# Motor-X.net
KiCad netlist of a schematic drawn in Altium Designer
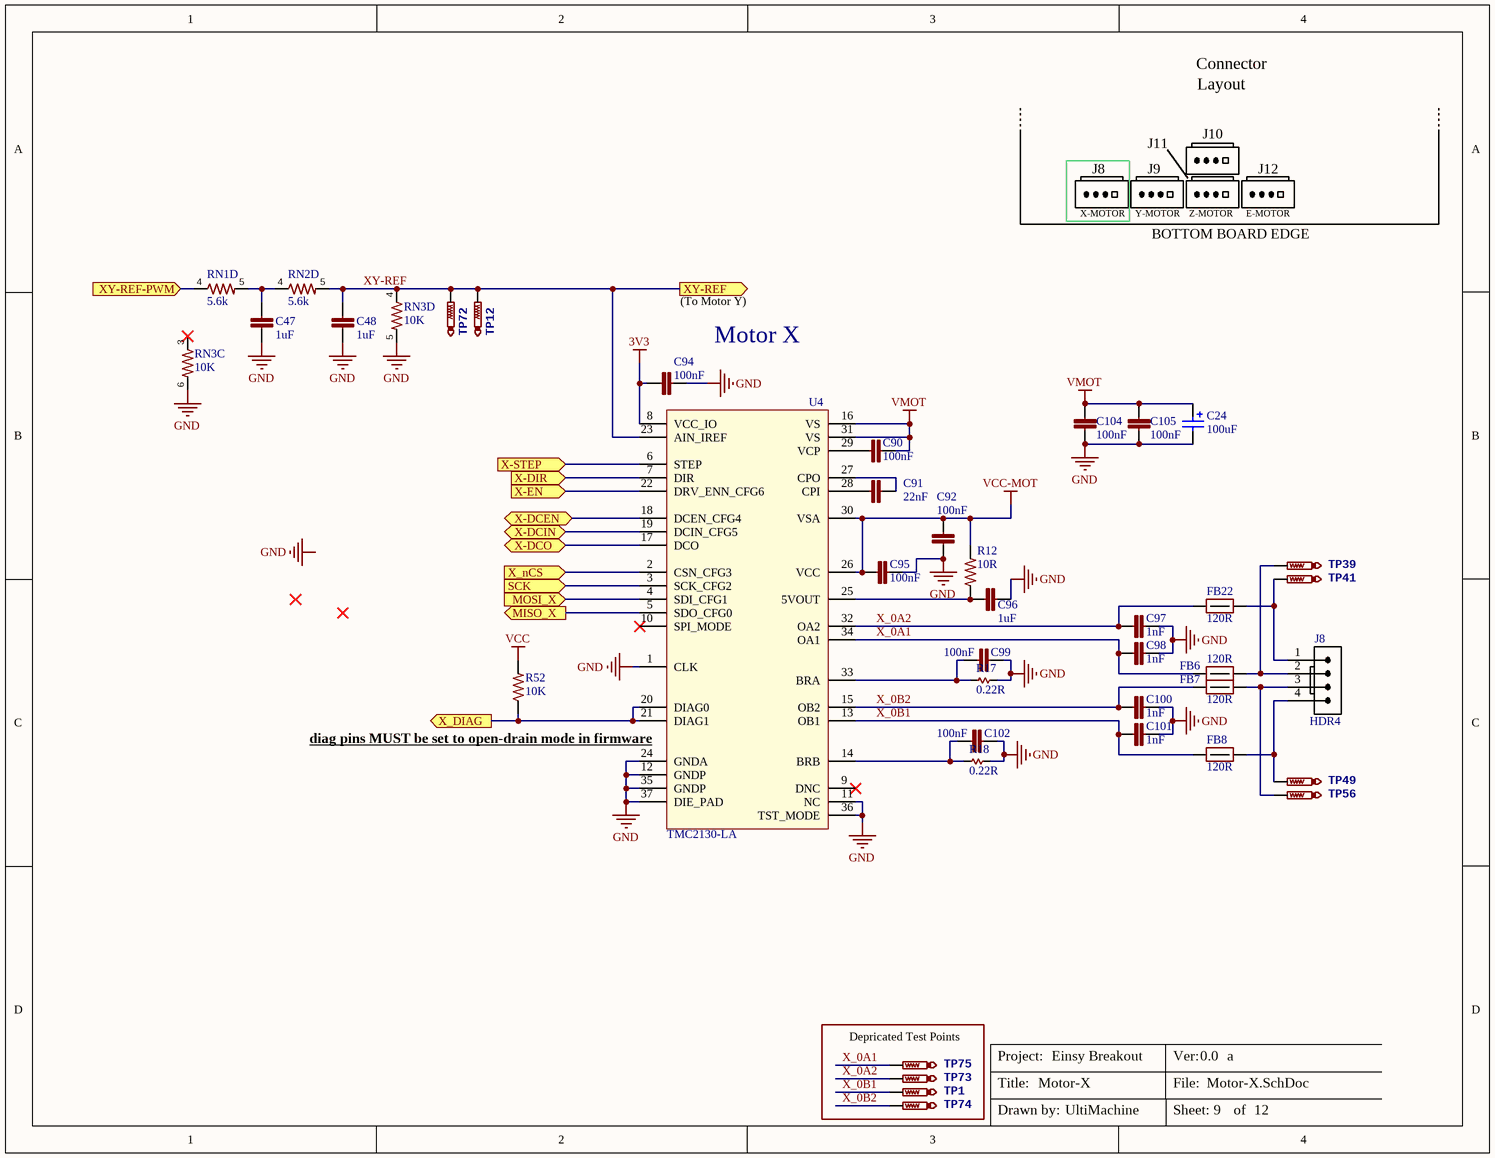
[diagram p0: Motor-X.SchDoc]

(export (version "E")
  (design (tool "Eeschema 10.0.6"))
  (components
    (comp (ref "C24")
      (value "100uF")
      (footprint "CAP-ELEC-063063077")
      (description "CAP ALUM 100UF 35V 20% SMD")
      (fields (field (name "MANUFACTURER") "Nichicon") (field (name "TOLERANCE") "+/- 20%"))
      (libsource (lib "3Delight") (part "UWT1V101MCL1GS"))
    )
    (comp (ref "C47")
      (value "1uF")
      (footprint "C0402")
      (description "CAP CER 0402 1uF 6.3V 10% X5R")
      (fields (field (name "MANUFACTURER") "Murata") (field (name "TOLERANCE") "+/- 10%"))
      (libsource (lib "3Delight") (part "GRM155R60J105KE19D"))
    )
    (comp (ref "C48")
      (value "1uF")
      (footprint "C0402")
      (description "CAP CER 0402 1uF 6.3V 10% X5R")
      (fields (field (name "MANUFACTURER") "Murata") (field (name "TOLERANCE") "+/- 10%"))
      (libsource (lib "3Delight") (part "GRM155R60J105KE19D"))
    )
    (comp (ref "C90")
      (value "100nF")
      (footprint "C0603")
      (description "CAP CER 0603 100nF 50V 10% X7R")
      (fields (field (name "MANUFACTURER") "Kemet") (field (name "TOLERANCE") "+/- 10%"))
      (libsource (lib "") (part "C0603C104K5RACTU_1"))
    )
    (comp (ref "C91")
      (value "22nF")
      (footprint "C0402")
      (description "CAP CER 0402 22nF ±10% 50V X7R")
      (fields (field (name "MANUFACTURER") "YAGEO") (field (name "TOLERANCE") "+/- 10%"))
      (libsource (lib "3Delight") (part "GCM155R71H223KA55D"))
    )
    (comp (ref "C92")
      (value "100nF")
      (footprint "C0402")
      (description "CAP CER 0402 100nF 16V 10% X7R")
      (fields (field (name "MANUFACTURER") "Murata") (field (name "TOLERANCE") "+/- 10%"))
      (libsource (lib "3Delight") (part "GRM155R71C104KA88D"))
    )
    (comp (ref "C94")
      (value "100nF")
      (footprint "C0402")
      (description "CAP CER 0402 100nF 16V 10% X7R")
      (fields (field (name "MANUFACTURER") "Murata") (field (name "TOLERANCE") "+/- 10%"))
      (libsource (lib "") (part "GRM155R71C104KA88D_1"))
    )
    (comp (ref "C95")
      (value "100nF")
      (footprint "C0402")
      (description "CAP CER 0402 100nF 16V 10% X7R")
      (fields (field (name "MANUFACTURER") "Murata") (field (name "TOLERANCE") "+/- 10%"))
      (libsource (lib "") (part "GRM155R71C104KA88D_1"))
    )
    (comp (ref "C96")
      (value "1uF")
      (footprint "C0402")
      (description "CAP CER 0402 1uF 6.3V 10% X5R")
      (fields (field (name "MANUFACTURER") "Murata") (field (name "TOLERANCE") "+/- 10%"))
      (libsource (lib "") (part "GRM155R60J105KE19D_1"))
    )
    (comp (ref "C97")
      (value "1nF")
      (footprint "C0603")
      (description "CAP CER 0603  1nF 50v 10% X7R")
      (fields (field (name "MANUFACTURER") "Kemet") (field (name "TOLERANCE") "+/- 10%"))
      (libsource (lib "3Delight") (part "C0603C102K5RACTU"))
    )
    (comp (ref "C98")
      (value "1nF")
      (footprint "C0603")
      (description "CAP CER 0603  1nF 50v 10% X7R")
      (fields (field (name "MANUFACTURER") "Kemet") (field (name "TOLERANCE") "+/- 10%"))
      (libsource (lib "3Delight") (part "C0603C102K5RACTU"))
    )
    (comp (ref "C99")
      (value "100nF")
      (footprint "C0603")
      (description "CAP CER 0603 100nF 50V 10% X7R")
      (fields (field (name "MANUFACTURER") "Kemet") (field (name "TOLERANCE") "+/- 10%"))
      (libsource (lib "3Delight") (part "C0603C104K5RACTU"))
    )
    (comp (ref "C100")
      (value "1nF")
      (footprint "C0603")
      (description "CAP CER 0603  1nF 50v 10% X7R")
      (fields (field (name "MANUFACTURER") "Kemet") (field (name "TOLERANCE") "+/- 10%"))
      (libsource (lib "3Delight") (part "C0603C102K5RACTU"))
    )
    (comp (ref "C101")
      (value "1nF")
      (footprint "C0603")
      (description "CAP CER 0603  1nF 50v 10% X7R")
      (fields (field (name "MANUFACTURER") "Kemet") (field (name "TOLERANCE") "+/- 10%"))
      (libsource (lib "3Delight") (part "C0603C102K5RACTU"))
    )
    (comp (ref "C102")
      (value "100nF")
      (footprint "C0603")
      (description "CAP CER 0603 100nF 50V 10% X7R")
      (fields (field (name "MANUFACTURER") "Kemet") (field (name "TOLERANCE") "+/- 10%"))
      (libsource (lib "3Delight") (part "C0603C104K5RACTU"))
    )
    (comp (ref "C104")
      (value "100nF")
      (footprint "C0603")
      (description "CAP CER 0603 100nF 50V 10% X7R")
      (fields (field (name "MANUFACTURER") "Kemet") (field (name "TOLERANCE") "+/- 10%"))
      (libsource (lib "") (part "C0603C104K5RACTU_2"))
    )
    (comp (ref "C105")
      (value "100nF")
      (footprint "C0603")
      (description "CAP CER 0603 100nF 50V 10% X7R")
      (fields (field (name "MANUFACTURER") "Kemet") (field (name "TOLERANCE") "+/- 10%"))
      (libsource (lib "") (part "C0603C104K5RACTU_2"))
    )
    (comp (ref "FB6")
      (value "120R")
      (footprint "FB0603")
      (description "FERRITE BEAD 120 OHM 0603 1LN")
      (fields (field (name "MANUFACTURER") "Samsung") (field (name "PART") "FERRITE 120R 3A 0603"))
      (libsource (lib "Inductors") (part "FERRITE 120R 3A 0603"))
    )
    (comp (ref "FB7")
      (value "120R")
      (footprint "FB0603")
      (description "FERRITE BEAD 120 OHM 0603 1LN")
      (fields (field (name "MANUFACTURER") "Samsung") (field (name "PART") "FERRITE 120R 3A 0603"))
      (libsource (lib "Inductors") (part "FERRITE 120R 3A 0603"))
    )
    (comp (ref "FB8")
      (value "120R")
      (footprint "FB0603")
      (description "FERRITE BEAD 120 OHM 0603 1LN")
      (fields (field (name "MANUFACTURER") "Samsung") (field (name "PART") "FERRITE 120R 3A 0603"))
      (libsource (lib "Inductors") (part "FERRITE 120R 3A 0603"))
    )
    (comp (ref "FB22")
      (value "120R")
      (footprint "FB0603")
      (description "FERRITE BEAD 120 OHM 0603 1LN")
      (fields (field (name "MANUFACTURER") "Samsung") (field (name "PART") "FERRITE 120R 3A 0603"))
      (libsource (lib "Inductors") (part "FERRITE 120R 3A 0603"))
    )
    (comp (ref "J8")
      (value "HDR4")
      (footprint "4POL254")
      (description "Molex 4 Pin Clip Connector")
      (fields (field (name "MANUFACTURER") "Molex") (field (name "PART") "4 Pin Conn"))
      (libsource (lib "3Delight") (part "CONN 4PIN 0.1{dblquote} VERT SHRD LOCK ALT"))
    )
    (comp (ref "R12")
      (value "10R")
      (footprint "R0402")
      (description "RES SMD 10 OHM 1% 1/16W 0402")
      (fields (field (name "MANUFACTURER") "Yageo") (field (name "TOLERANCE") "+/- 1%"))
      (libsource (lib "3Delight") (part "RC0402FR-0710RL"))
    )
    (comp (ref "R17")
      (value "0.22R")
      (footprint "R1206")
      (description "RES SMD 0.22 OHM 1% 1/3W 1206")
      (fields (field (name "MANUFACTURER") "Panasonic") (field (name "TOLERANCE") "+/- 1%"))
      (libsource (lib "Resistors") (part "0.22R 1% 1206"))
    )
    (comp (ref "R18")
      (value "0.22R")
      (footprint "R1206")
      (description "RES SMD 0.22 OHM 1% 1/3W 1206")
      (fields (field (name "MANUFACTURER") "Panasonic") (field (name "TOLERANCE") "+/- 1%"))
      (libsource (lib "Resistors") (part "0.22R 1% 1206"))
    )
    (comp (ref "R52")
      (value "10K")
      (footprint "R0402")
      (description "RES SMD 10K OHM 1% 1/16W 0402")
      (fields (field (name "MANUFACTURER") "Yageo") (field (name "PART") "10k 1% 0402"))
      (libsource (lib "3Delight") (part "RC0402FR-0710KP"))
    )
    (comp (ref "RN1")
      (value "5.6k")
      (footprint "CAY16")
      (description "RES ARRAY 4 RES 5.6K OHM 1206")
      (fields (field (name "MANUFACTURER") "Bourns") (field (name "TOLERANCE") "+/- 5%"))
      (libsource (lib "Resistors") (part "5.6k x 4 5% 1206"))
    )
    (comp (ref "RN2")
      (value "5.6k")
      (footprint "CAY16")
      (description "RES ARRAY 4 RES 5.6K OHM 1206")
      (fields (field (name "MANUFACTURER") "Bourns") (field (name "TOLERANCE") "+/- 5%"))
      (libsource (lib "Resistors") (part "5.6k x 4 5% 1206"))
    )
    (comp (ref "RN3")
      (value "10K")
      (footprint "CAY16")
      (description "RES ARRAY 4 RES 10K 1206 62.5mW 5%")
      (fields (field (name "MANUFACTURER") "Bourns") (field (name "TOLERANCE") "+/- 5%"))
      (libsource (lib "3Delight") (part "CAY16-103J4LF"))
    )
    (comp (ref "TP1")
      (value "TestPoint")
      (footprint "TP1-27")
      (description "Test Point")
      (libsource (lib "3Delight") (part "TestPoint"))
    )
    (comp (ref "TP12")
      (value "TestPoint")
      (footprint "TP1-27")
      (description "Test Point")
      (libsource (lib "") (part "TestPoint_1"))
    )
    (comp (ref "TP39")
      (value "TestPoint")
      (footprint "TP1-27")
      (description "Test Point")
      (libsource (lib "3Delight") (part "TestPoint"))
    )
    (comp (ref "TP41")
      (value "TestPoint")
      (footprint "TP1-27")
      (description "Test Point")
      (libsource (lib "3Delight") (part "TestPoint"))
    )
    (comp (ref "TP49")
      (value "TestPoint")
      (footprint "TP1-27")
      (description "Test Point")
      (libsource (lib "3Delight") (part "TestPoint"))
    )
    (comp (ref "TP56")
      (value "TestPoint")
      (footprint "TP1-27")
      (description "Test Point")
      (libsource (lib "3Delight") (part "TestPoint"))
    )
    (comp (ref "TP72")
      (value "TestPoint")
      (footprint "TP1-27")
      (description "Test Point")
      (libsource (lib "") (part "TestPoint_1"))
    )
    (comp (ref "TP73")
      (value "TestPoint")
      (footprint "TP1-27")
      (description "Test Point")
      (libsource (lib "3Delight") (part "TestPoint"))
    )
    (comp (ref "TP74")
      (value "TestPoint")
      (footprint "TP1-27")
      (description "Test Point")
      (libsource (lib "3Delight") (part "TestPoint"))
    )
    (comp (ref "TP75")
      (value "TestPoint")
      (footprint "TP1-27")
      (description "Test Point")
      (libsource (lib "3Delight") (part "TestPoint"))
    )
    (comp (ref "U4")
      (value "TMC2130-LA")
      (footprint "QFN36-50P500X600X900_HS-37N")
      (description "IC STEPPER MOTOR DVR SPI 36QFN")
      (fields (field (name "MANUFACTURER") "Trinamic") (field (name "PART") "TMC2130"))
      (libsource (lib "ICs-Motor Controller") (part "TMC2130-LA-T"))
    )
  )
  (nets
    (net (code "1") (name "/MISO_X") (class "Default")
      (node (ref "U4") (pin "5") (pinfunction "SDO_CFG0_5") (pintype "passive"))
    )
    (net (code "2") (name "/MOSI_X") (class "Default")
      (node (ref "U4") (pin "4") (pinfunction "SDI_CFG1_4") (pintype "passive"))
    )
    (net (code "3") (name "/SCK") (class "Default")
      (node (ref "U4") (pin "3") (pinfunction "SCK_CFG2_3") (pintype "passive"))
    )
    (net (code "4") (name "/X-DCEN") (class "Default")
      (node (ref "U4") (pin "18") (pinfunction "DCEN_CFG4_18") (pintype "passive"))
    )
    (net (code "5") (name "/X-DCIN") (class "Default")
      (node (ref "U4") (pin "19") (pinfunction "DCIN_CFG5_19") (pintype "passive"))
    )
    (net (code "6") (name "/X-DCO") (class "Default")
      (node (ref "U4") (pin "17") (pinfunction "DCO_17") (pintype "passive"))
    )
    (net (code "7") (name "/X-DIR") (class "Default")
      (node (ref "U4") (pin "7") (pinfunction "DIR_7") (pintype "passive"))
    )
    (net (code "8") (name "/X-EN") (class "Default")
      (node (ref "U4") (pin "22") (pinfunction "DRV_ENN_CFG6_22") (pintype "passive"))
    )
    (net (code "9") (name "/X-STEP") (class "Default")
      (node (ref "U4") (pin "6") (pinfunction "STEP_6") (pintype "passive"))
    )
    (net (code "10") (name "/XY-REF") (class "Default")
      (node (ref "C48") (pin "1") (pinfunction "1_1") (pintype "passive"))
      (node (ref "RN2") (pin "5") (pinfunction "2_5") (pintype "passive"))
      (node (ref "RN3") (pin "4") (pinfunction "1_4") (pintype "passive"))
      (node (ref "TP12") (pin "TP") (pinfunction "TP_TP") (pintype "passive"))
      (node (ref "TP72") (pin "TP") (pinfunction "TP_TP") (pintype "passive"))
      (node (ref "U4") (pin "23") (pinfunction "AIN_IREF_23") (pintype "passive"))
    )
    (net (code "11") (name "/XY-REF-PWM") (class "Default")
      (node (ref "RN1") (pin "4") (pinfunction "1_4") (pintype "passive"))
    )
    (net (code "12") (name "/X_0A1") (class "Default")
      (node (ref "C98") (pin "1") (pinfunction "1_1") (pintype "passive"))
      (node (ref "FB6") (pin "1") (pinfunction "1_1") (pintype "passive"))
      (node (ref "TP75") (pin "TP") (pinfunction "TP_TP") (pintype "passive"))
      (node (ref "U4") (pin "34") (pinfunction "OA1_34") (pintype "passive"))
    )
    (net (code "13") (name "/X_0A2") (class "Default")
      (node (ref "C97") (pin "1") (pinfunction "1_1") (pintype "passive"))
      (node (ref "FB22") (pin "1") (pinfunction "1_1") (pintype "passive"))
      (node (ref "TP73") (pin "TP") (pinfunction "TP_TP") (pintype "passive"))
      (node (ref "U4") (pin "32") (pinfunction "OA2_32") (pintype "passive"))
    )
    (net (code "14") (name "/X_0B1") (class "Default")
      (node (ref "C101") (pin "1") (pinfunction "1_1") (pintype "passive"))
      (node (ref "FB8") (pin "1") (pinfunction "1_1") (pintype "passive"))
      (node (ref "TP1") (pin "TP") (pinfunction "TP_TP") (pintype "passive"))
      (node (ref "U4") (pin "13") (pinfunction "OB1_13") (pintype "passive"))
    )
    (net (code "15") (name "/X_0B2") (class "Default")
      (node (ref "C100") (pin "1") (pinfunction "1_1") (pintype "passive"))
      (node (ref "FB7") (pin "1") (pinfunction "1_1") (pintype "passive"))
      (node (ref "TP74") (pin "TP") (pinfunction "TP_TP") (pintype "passive"))
      (node (ref "U4") (pin "15") (pinfunction "OB2_15") (pintype "passive"))
    )
    (net (code "16") (name "/X_DIAG") (class "Default")
      (node (ref "R52") (pin "1") (pinfunction "1_1") (pintype "passive"))
      (node (ref "U4") (pin "20") (pinfunction "DIAG0_20") (pintype "passive"))
      (node (ref "U4") (pin "21") (pinfunction "DIAG1_21") (pintype "passive"))
    )
    (net (code "17") (name "/X_nCS") (class "Default")
      (node (ref "U4") (pin "2") (pinfunction "CSN_CFG3_2") (pintype "passive"))
    )
    (net (code "18") (name "3V3") (class "Default")
      (node (ref "C94") (pin "2") (pinfunction "2_2") (pintype "passive"))
      (node (ref "U4") (pin "8") (pinfunction "VCC_IO_8") (pintype "passive"))
    )
    (net (code "19") (name "GND") (class "Default")
      (node (ref "C100") (pin "2") (pinfunction "2_2") (pintype "passive"))
      (node (ref "C101") (pin "2") (pinfunction "2_2") (pintype "passive"))
      (node (ref "C102") (pin "1") (pinfunction "1_1") (pintype "passive"))
      (node (ref "C104") (pin "1") (pinfunction "1_1") (pintype "passive"))
      (node (ref "C105") (pin "1") (pinfunction "1_1") (pintype "passive"))
      (node (ref "C24") (pin "2") (pinfunction "2_2") (pintype "passive"))
      (node (ref "C47") (pin "2") (pinfunction "2_2") (pintype "passive"))
      (node (ref "C48") (pin "2") (pinfunction "2_2") (pintype "passive"))
      (node (ref "C92") (pin "1") (pinfunction "1_1") (pintype "passive"))
      (node (ref "C94") (pin "1") (pinfunction "1_1") (pintype "passive"))
      (node (ref "C95") (pin "1") (pinfunction "1_1") (pintype "passive"))
      (node (ref "C96") (pin "2") (pinfunction "2_2") (pintype "passive"))
      (node (ref "C97") (pin "2") (pinfunction "2_2") (pintype "passive"))
      (node (ref "C98") (pin "2") (pinfunction "2_2") (pintype "passive"))
      (node (ref "C99") (pin "1") (pinfunction "1_1") (pintype "passive"))
      (node (ref "R17") (pin "2") (pinfunction "2_2") (pintype "passive"))
      (node (ref "R18") (pin "2") (pinfunction "2_2") (pintype "passive"))
      (node (ref "RN3") (pin "5") (pinfunction "2_5") (pintype "passive"))
      (node (ref "RN3") (pin "6") (pinfunction "2_6") (pintype "passive"))
      (node (ref "U4") (pin "1") (pinfunction "CLK_1") (pintype "passive"))
      (node (ref "U4") (pin "11") (pinfunction "NC_11") (pintype "passive"))
      (node (ref "U4") (pin "12") (pinfunction "GNDP_12") (pintype "passive"))
      (node (ref "U4") (pin "24") (pinfunction "GNDA_24") (pintype "passive"))
      (node (ref "U4") (pin "35") (pinfunction "GNDP_35") (pintype "passive"))
      (node (ref "U4") (pin "36") (pinfunction "TST_MODE_36") (pintype "passive"))
      (node (ref "U4") (pin "37") (pinfunction "DIE_PAD_37") (pintype "passive"))
    )
    (net (code "20") (name "Net-(FB6-Pad2)") (class "Default")
      (node (ref "FB6") (pin "2") (pinfunction "2_2") (pintype "passive"))
      (node (ref "J8") (pin "2") (pinfunction "2_2") (pintype "passive"))
      (node (ref "TP39") (pin "TP") (pinfunction "TP_TP") (pintype "passive"))
    )
    (net (code "21") (name "Net-(FB7-Pad2)") (class "Default")
      (node (ref "FB7") (pin "2") (pinfunction "2_2") (pintype "passive"))
      (node (ref "J8") (pin "3") (pinfunction "3_3") (pintype "passive"))
      (node (ref "TP56") (pin "TP") (pinfunction "TP_TP") (pintype "passive"))
    )
    (net (code "22") (name "Net-(FB8-Pad2)") (class "Default")
      (node (ref "FB8") (pin "2") (pinfunction "2_2") (pintype "passive"))
      (node (ref "J8") (pin "4") (pinfunction "4_4") (pintype "passive"))
      (node (ref "TP49") (pin "TP") (pinfunction "TP_TP") (pintype "passive"))
    )
    (net (code "23") (name "Net-(FB22-Pad2)") (class "Default")
      (node (ref "FB22") (pin "2") (pinfunction "2_2") (pintype "passive"))
      (node (ref "J8") (pin "1") (pinfunction "1_1") (pintype "passive"))
      (node (ref "TP41") (pin "TP") (pinfunction "TP_TP") (pintype "passive"))
    )
    (net (code "24") (name "Net-(RN1D-2)") (class "Default")
      (node (ref "C47") (pin "1") (pinfunction "1_1") (pintype "passive"))
      (node (ref "RN1") (pin "5") (pinfunction "2_5") (pintype "passive"))
      (node (ref "RN2") (pin "4") (pinfunction "1_4") (pintype "passive"))
    )
    (net (code "25") (name "Net-(U4-5VOUT)") (class "Default")
      (node (ref "C96") (pin "1") (pinfunction "1_1") (pintype "passive"))
      (node (ref "R12") (pin "1") (pinfunction "1_1") (pintype "passive"))
      (node (ref "U4") (pin "25") (pinfunction "5VOUT_25") (pintype "passive"))
    )
    (net (code "26") (name "Net-(U4-BRA)") (class "Default")
      (node (ref "C99") (pin "2") (pinfunction "2_2") (pintype "passive"))
      (node (ref "R17") (pin "1") (pinfunction "1_1") (pintype "passive"))
      (node (ref "U4") (pin "33") (pinfunction "BRA_33") (pintype "passive"))
    )
    (net (code "27") (name "Net-(U4-BRB)") (class "Default")
      (node (ref "C102") (pin "2") (pinfunction "2_2") (pintype "passive"))
      (node (ref "R18") (pin "1") (pinfunction "1_1") (pintype "passive"))
      (node (ref "U4") (pin "14") (pinfunction "BRB_14") (pintype "passive"))
    )
    (net (code "28") (name "Net-(U4-CPI)") (class "Default")
      (node (ref "C91") (pin "1") (pinfunction "1_1") (pintype "passive"))
      (node (ref "U4") (pin "28") (pinfunction "CPI_28") (pintype "passive"))
    )
    (net (code "29") (name "Net-(U4-CPO)") (class "Default")
      (node (ref "C91") (pin "2") (pinfunction "2_2") (pintype "passive"))
      (node (ref "U4") (pin "27") (pinfunction "CPO_27") (pintype "passive"))
    )
    (net (code "30") (name "Net-(U4-VCP)") (class "Default")
      (node (ref "C90") (pin "1") (pinfunction "1_1") (pintype "passive"))
      (node (ref "U4") (pin "29") (pinfunction "VCP_29") (pintype "passive"))
    )
    (net (code "31") (name "VCC") (class "Default")
      (node (ref "R52") (pin "2") (pinfunction "2_2") (pintype "passive"))
    )
    (net (code "32") (name "VCC-MOT") (class "Default")
      (node (ref "C92") (pin "2") (pinfunction "2_2") (pintype "passive"))
      (node (ref "C95") (pin "2") (pinfunction "2_2") (pintype "passive"))
      (node (ref "R12") (pin "2") (pinfunction "2_2") (pintype "passive"))
      (node (ref "U4") (pin "26") (pinfunction "VCC_26") (pintype "passive"))
      (node (ref "U4") (pin "30") (pinfunction "VSA_30") (pintype "passive"))
    )
    (net (code "33") (name "VMOT") (class "Default")
      (node (ref "C104") (pin "2") (pinfunction "2_2") (pintype "passive"))
      (node (ref "C105") (pin "2") (pinfunction "2_2") (pintype "passive"))
      (node (ref "C24") (pin "1") (pinfunction "1_1") (pintype "passive"))
      (node (ref "C90") (pin "2") (pinfunction "2_2") (pintype "passive"))
      (node (ref "U4") (pin "16") (pinfunction "VS_16") (pintype "passive"))
      (node (ref "U4") (pin "31") (pinfunction "VS_31") (pintype "passive"))
    )
    (net (code "34") (name "unconnected-(RN3C-1-Pad3)") (class "Default")
      (node (ref "RN3") (pin "3") (pinfunction "1_3") (pintype "passive+no_connect"))
    )
    (net (code "35") (name "unconnected-(U4-DNC-Pad9)") (class "Default")
      (node (ref "U4") (pin "9") (pinfunction "DNC_9") (pintype "passive+no_connect"))
    )
    (net (code "36") (name "unconnected-(U4-SPI_MODE-Pad10)") (class "Default")
      (node (ref "U4") (pin "10") (pinfunction "SPI_MODE_10") (pintype "passive+no_connect"))
    )
  )
)
